# wbz451pe.net
KiCad netlist of a schematic drawn in EAGLE
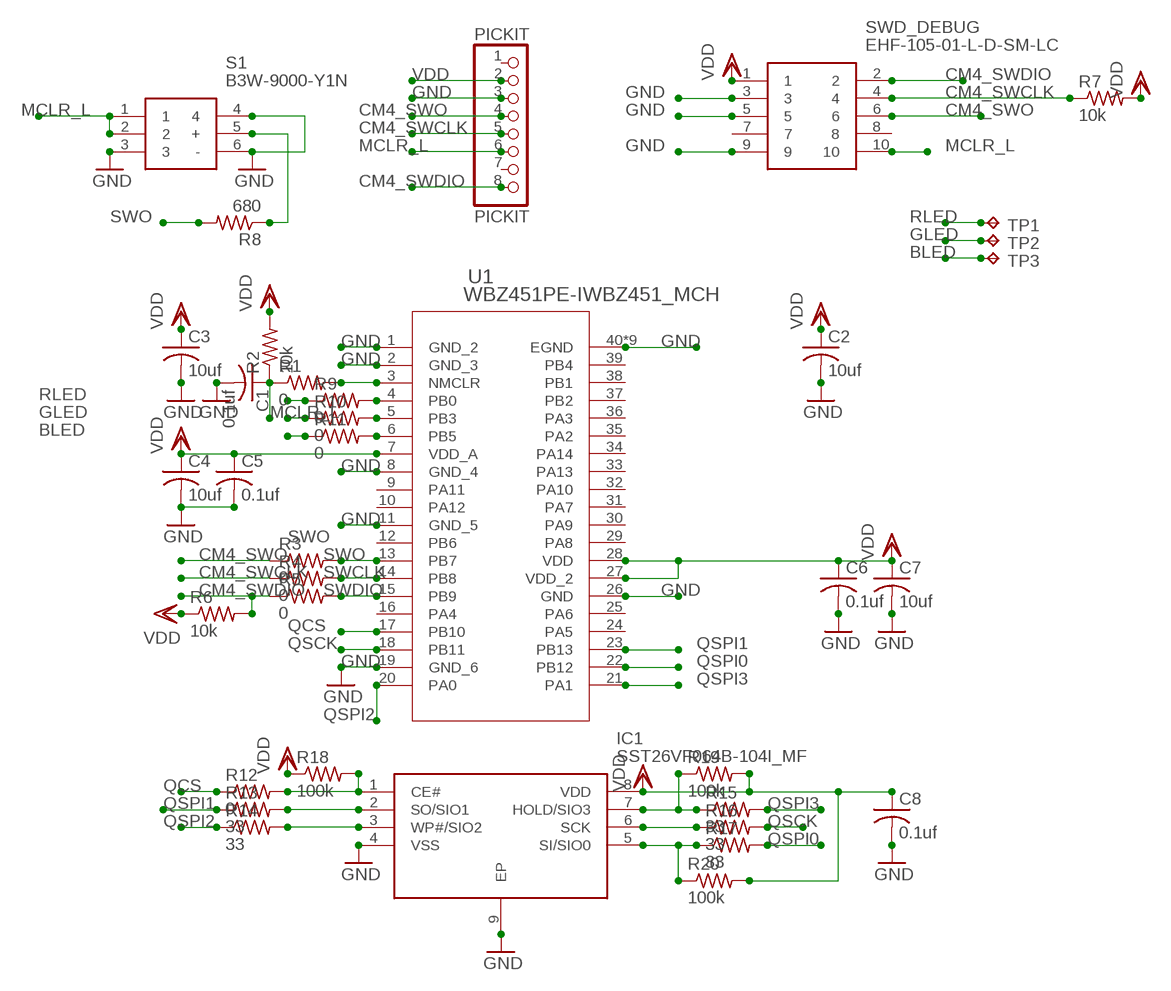
[diagram p0: schematic, sheet 1]

(export (version "E")
  (design (tool "Eeschema 10.0.6"))
  (components
    (comp (ref "C1")
      (value "0.1uf")
      (footprint "eagle-import:C0805")
      (libsource (lib "eagle-import") (part "C-USC0805"))
    )
    (comp (ref "C2")
      (value "10uf")
      (footprint "eagle-import:C0805")
      (libsource (lib "eagle-import") (part "C-USC0805"))
    )
    (comp (ref "C3")
      (value "10uf")
      (footprint "eagle-import:C0805")
      (libsource (lib "eagle-import") (part "C-USC0805"))
    )
    (comp (ref "C4")
      (value "10uf")
      (footprint "eagle-import:C0805")
      (libsource (lib "eagle-import") (part "C-USC0805"))
    )
    (comp (ref "C5")
      (value "0.1uf")
      (footprint "eagle-import:C0805")
      (libsource (lib "eagle-import") (part "C-USC0805"))
    )
    (comp (ref "C6")
      (value "0.1uf")
      (footprint "eagle-import:C0805")
      (libsource (lib "eagle-import") (part "C-USC0805"))
    )
    (comp (ref "C7")
      (value "10uf")
      (footprint "eagle-import:C0805")
      (libsource (lib "eagle-import") (part "C-USC0805"))
    )
    (comp (ref "C8")
      (value "0.1uf")
      (footprint "eagle-import:C0805")
      (libsource (lib "eagle-import") (part "C-USC0805"))
    )
    (comp (ref "IC1")
      (value "SST26VF064B-104I_MF")
      (footprint "eagle-import:SON127P600X500X80-9N")
      (fields
        (field (name "MANUFACTURER_PART_NUMBER") "SST26VF064B-104I/MF")
        (field (name "MOUSER_PART_NUMBER") "579-ST26VF064B104IMF")
      )
      (libsource (lib "eagle-import") (part "SST26VF064B-104I_MF"))
    )
    (comp (ref "PICKIT")
      (value "PICKIT")
      (footprint "eagle-import:1X08")
      (libsource (lib "eagle-import") (part "PINHD-1X8"))
    )
    (comp (ref "R1")
      (value "0")
      (footprint "eagle-import:M0805")
      (libsource (lib "eagle-import") (part "R-US_M0805"))
    )
    (comp (ref "R2")
      (value "10k")
      (footprint "eagle-import:M0805")
      (libsource (lib "eagle-import") (part "R-US_M0805"))
    )
    (comp (ref "R3")
      (value "0")
      (footprint "eagle-import:M0805")
      (libsource (lib "eagle-import") (part "R-US_M0805"))
    )
    (comp (ref "R4")
      (value "0")
      (footprint "eagle-import:M0805")
      (libsource (lib "eagle-import") (part "R-US_M0805"))
    )
    (comp (ref "R5")
      (value "0")
      (footprint "eagle-import:M0805")
      (libsource (lib "eagle-import") (part "R-US_M0805"))
    )
    (comp (ref "R6")
      (value "10k")
      (footprint "eagle-import:M0805")
      (libsource (lib "eagle-import") (part "R-US_M0805"))
    )
    (comp (ref "R7")
      (value "10k")
      (footprint "eagle-import:M0805")
      (libsource (lib "eagle-import") (part "R-US_M0805"))
    )
    (comp (ref "R8")
      (value "680")
      (footprint "eagle-import:M0805")
      (libsource (lib "eagle-import") (part "R-US_M0805"))
    )
    (comp (ref "R9")
      (value "0")
      (footprint "eagle-import:M0805")
      (libsource (lib "eagle-import") (part "R-US_M0805"))
    )
    (comp (ref "R10")
      (value "0")
      (footprint "eagle-import:M0805")
      (libsource (lib "eagle-import") (part "R-US_M0805"))
    )
    (comp (ref "R11")
      (value "0")
      (footprint "eagle-import:M0805")
      (libsource (lib "eagle-import") (part "R-US_M0805"))
    )
    (comp (ref "R12")
      (value "0")
      (footprint "eagle-import:R0603")
      (libsource (lib "eagle-import") (part "R-US_R0603"))
    )
    (comp (ref "R13")
      (value "33")
      (footprint "eagle-import:R0603")
      (libsource (lib "eagle-import") (part "R-US_R0603"))
    )
    (comp (ref "R14")
      (value "33")
      (footprint "eagle-import:R0603")
      (libsource (lib "eagle-import") (part "R-US_R0603"))
    )
    (comp (ref "R15")
      (value "33")
      (footprint "eagle-import:R0603")
      (libsource (lib "eagle-import") (part "R-US_R0603"))
    )
    (comp (ref "R16")
      (value "33")
      (footprint "eagle-import:R0603")
      (libsource (lib "eagle-import") (part "R-US_R0603"))
    )
    (comp (ref "R17")
      (value "33")
      (footprint "eagle-import:R0603")
      (libsource (lib "eagle-import") (part "R-US_R0603"))
    )
    (comp (ref "R18")
      (value "100k")
      (footprint "eagle-import:R0603")
      (libsource (lib "eagle-import") (part "R-US_R0603"))
    )
    (comp (ref "R19")
      (value "100k")
      (footprint "eagle-import:R0603")
      (libsource (lib "eagle-import") (part "R-US_R0603"))
    )
    (comp (ref "R20")
      (value "100k")
      (footprint "eagle-import:R0603")
      (libsource (lib "eagle-import") (part "R-US_R0603"))
    )
    (comp (ref "S1")
      (value "B3W-9000-Y1N")
      (footprint "eagle-import:B3W-9_1-LED")
      (fields
        (field (name "MOUSER_PART_NUMBER") "653-B3W-9000-Y1N")
        (field (name "RS_PART_NUMBER") "0492777P")
      )
      (libsource (lib "eagle-import") (part "B3W-9000-Y1N"))
    )
    (comp (ref "SWD_DEBUG")
      (value "EHF-105-01-L-D-SM-LC")
      (footprint "eagle-import:EHF-105-01-XX-D-SM-LC")
      (fields (field (name "MOUSER_PART_NUMBER") "200-EHF10501LDSMLC"))
      (libsource (lib "eagle-import") (part "EHF-105-01-L-D-SM-LC"))
    )
    (comp (ref "TP1")
      (value "TPPAD1-13")
      (footprint "eagle-import:P1-13")
      (libsource (lib "eagle-import") (part "TPPAD1-13"))
    )
    (comp (ref "TP2")
      (value "TPPAD1-13")
      (footprint "eagle-import:P1-13")
      (libsource (lib "eagle-import") (part "TPPAD1-13"))
    )
    (comp (ref "TP3")
      (value "TPPAD1-13")
      (footprint "eagle-import:P1-13")
      (libsource (lib "eagle-import") (part "TPPAD1-13"))
    )
    (comp (ref "U1")
      (value "WBZ451PE-IWBZ451_MCH")
      (footprint "eagle-import:WBZ451_MCH")
      (fields
        (field (name "MANUFACTURER_PART_NUMBER") "WBZ451PE-I")
        (field (name "COPYRIGHT") "Copyright (C) 2024 Ultra Librarian. All rights reserved.")
      )
      (libsource (lib "eagle-import") (part "WBZ451PE-IWBZ451_MCH"))
    )
  )
  (nets
    (net (code "1") (name "/BLED") (class "Default")
      (node (ref "R11") (pin "1") (pinfunction "1_1") (pintype "passive"))
      (node (ref "TP3") (pin "TP") (pinfunction "TP_TP") (pintype "input"))
    )
    (net (code "2") (name "/CM4_SWCLK") (class "Default")
      (node (ref "PICKIT") (pin "5") (pinfunction "5_5") (pintype "passive"))
      (node (ref "R4") (pin "1") (pinfunction "1_1") (pintype "passive"))
      (node (ref "R7") (pin "1") (pinfunction "1_1") (pintype "passive"))
      (node (ref "SWD_DEBUG") (pin "4") (pinfunction "4_4") (pintype "bidirectional"))
    )
    (net (code "3") (name "/CM4_SWDIO") (class "Default")
      (node (ref "PICKIT") (pin "8") (pinfunction "8_8") (pintype "passive"))
      (node (ref "R5") (pin "1") (pinfunction "1_1") (pintype "passive"))
      (node (ref "R6") (pin "2") (pinfunction "2_2") (pintype "passive"))
      (node (ref "SWD_DEBUG") (pin "2") (pinfunction "2_2") (pintype "bidirectional"))
    )
    (net (code "4") (name "/CM4_SWO") (class "Default")
      (node (ref "PICKIT") (pin "4") (pinfunction "4_4") (pintype "passive"))
      (node (ref "R3") (pin "1") (pinfunction "1_1") (pintype "passive"))
      (node (ref "SWD_DEBUG") (pin "6") (pinfunction "6_6") (pintype "bidirectional"))
    )
    (net (code "5") (name "/GLED") (class "Default")
      (node (ref "R10") (pin "1") (pinfunction "1_1") (pintype "passive"))
      (node (ref "TP2") (pin "TP") (pinfunction "TP_TP") (pintype "input"))
    )
    (net (code "6") (name "/MCLR_L") (class "Default")
      (node (ref "C1") (pin "1") (pinfunction "1_1") (pintype "passive"))
      (node (ref "PICKIT") (pin "6") (pinfunction "6_6") (pintype "passive"))
      (node (ref "R1") (pin "1") (pinfunction "1_1") (pintype "passive"))
      (node (ref "R2") (pin "1") (pinfunction "1_1") (pintype "passive"))
      (node (ref "S1") (pin "1") (pinfunction "1_1") (pintype "bidirectional"))
      (node (ref "S1") (pin "2") (pinfunction "2_2") (pintype "bidirectional"))
      (node (ref "SWD_DEBUG") (pin "10") (pinfunction "10_10") (pintype "bidirectional"))
    )
    (net (code "7") (name "/QCS") (class "Default")
      (node (ref "R12") (pin "1") (pinfunction "1_1") (pintype "passive"))
      (node (ref "U1") (pin "17") (pinfunction "PB10_17") (pintype "bidirectional"))
    )
    (net (code "8") (name "/QSCK") (class "Default")
      (node (ref "R16") (pin "2") (pinfunction "2_2") (pintype "passive"))
      (node (ref "U1") (pin "18") (pinfunction "PB11_18") (pintype "bidirectional"))
    )
    (net (code "9") (name "/QSPI0") (class "Default")
      (node (ref "R17") (pin "2") (pinfunction "2_2") (pintype "passive"))
      (node (ref "U1") (pin "22") (pinfunction "PB12_22") (pintype "bidirectional"))
    )
    (net (code "10") (name "/QSPI1") (class "Default")
      (node (ref "R13") (pin "1") (pinfunction "1_1") (pintype "passive"))
      (node (ref "U1") (pin "23") (pinfunction "PB13_23") (pintype "bidirectional"))
    )
    (net (code "11") (name "/QSPI2") (class "Default")
      (node (ref "R14") (pin "1") (pinfunction "1_1") (pintype "passive"))
      (node (ref "U1") (pin "20") (pinfunction "PA0_20") (pintype "bidirectional"))
    )
    (net (code "12") (name "/QSPI3") (class "Default")
      (node (ref "R15") (pin "2") (pinfunction "2_2") (pintype "passive"))
      (node (ref "U1") (pin "21") (pinfunction "PA1_21") (pintype "bidirectional"))
    )
    (net (code "13") (name "/RLED") (class "Default")
      (node (ref "R9") (pin "1") (pinfunction "1_1") (pintype "passive"))
      (node (ref "TP1") (pin "TP") (pinfunction "TP_TP") (pintype "input"))
    )
    (net (code "14") (name "/SWCLK") (class "Default")
      (node (ref "R4") (pin "2") (pinfunction "2_2") (pintype "passive"))
      (node (ref "U1") (pin "14") (pinfunction "PB8_14") (pintype "bidirectional"))
    )
    (net (code "15") (name "/SWDIO") (class "Default")
      (node (ref "R5") (pin "2") (pinfunction "2_2") (pintype "passive"))
      (node (ref "U1") (pin "15") (pinfunction "PB9_15") (pintype "bidirectional"))
    )
    (net (code "16") (name "/SWO") (class "Default")
      (node (ref "R3") (pin "2") (pinfunction "2_2") (pintype "passive"))
      (node (ref "R8") (pin "2") (pinfunction "2_2") (pintype "passive"))
      (node (ref "U1") (pin "13") (pinfunction "PB7_13") (pintype "bidirectional"))
    )
    (net (code "17") (name "GND") (class "Default")
      (node (ref "C1") (pin "2") (pinfunction "2_2") (pintype "passive"))
      (node (ref "C2") (pin "2") (pinfunction "2_2") (pintype "passive"))
      (node (ref "C3") (pin "2") (pinfunction "2_2") (pintype "passive"))
      (node (ref "C4") (pin "2") (pinfunction "2_2") (pintype "passive"))
      (node (ref "C5") (pin "2") (pinfunction "2_2") (pintype "passive"))
      (node (ref "C6") (pin "2") (pinfunction "2_2") (pintype "passive"))
      (node (ref "C7") (pin "2") (pinfunction "2_2") (pintype "passive"))
      (node (ref "C8") (pin "2") (pinfunction "2_2") (pintype "passive"))
      (node (ref "IC1") (pin "4") (pinfunction "VSS_4") (pintype "bidirectional"))
      (node (ref "IC1") (pin "9") (pinfunction "EP_9") (pintype "bidirectional"))
      (node (ref "PICKIT") (pin "3") (pinfunction "3_3") (pintype "passive"))
      (node (ref "S1") (pin "3") (pinfunction "3_3") (pintype "bidirectional"))
      (node (ref "S1") (pin "4") (pinfunction "4_4") (pintype "bidirectional"))
      (node (ref "S1") (pin "6") (pinfunction "-_6") (pintype "bidirectional"))
      (node (ref "SWD_DEBUG") (pin "3") (pinfunction "3_3") (pintype "bidirectional"))
      (node (ref "SWD_DEBUG") (pin "5") (pinfunction "5_5") (pintype "bidirectional"))
      (node (ref "SWD_DEBUG") (pin "9") (pinfunction "9_9") (pintype "bidirectional"))
      (node (ref "U1") (pin "1") (pinfunction "GND_2_1") (pintype "passive"))
      (node (ref "U1") (pin "11") (pinfunction "GND_5_11") (pintype "passive"))
      (node (ref "U1") (pin "19") (pinfunction "GND_6_19") (pintype "passive"))
      (node (ref "U1") (pin "2") (pinfunction "GND_3_2") (pintype "passive"))
      (node (ref "U1") (pin "26") (pinfunction "GND_26") (pintype "passive"))
      (node (ref "U1") (pin "40") (pinfunction "EGND_40") (pintype "passive"))
      (node (ref "U1") (pin "41") (pinfunction "EGND_41") (pintype "passive"))
      (node (ref "U1") (pin "42") (pinfunction "EGND_42") (pintype "passive"))
      (node (ref "U1") (pin "43") (pinfunction "EGND_43") (pintype "passive"))
      (node (ref "U1") (pin "44") (pinfunction "EGND_44") (pintype "passive"))
      (node (ref "U1") (pin "45") (pinfunction "EGND_45") (pintype "passive"))
      (node (ref "U1") (pin "46") (pinfunction "EGND_46") (pintype "passive"))
      (node (ref "U1") (pin "47") (pinfunction "EGND_47") (pintype "passive"))
      (node (ref "U1") (pin "48") (pinfunction "EGND_48") (pintype "passive"))
      (node (ref "U1") (pin "8") (pinfunction "GND_4_8") (pintype "passive"))
    )
    (net (code "18") (name "Net-(IC1-CE#)") (class "Default")
      (node (ref "IC1") (pin "1") (pinfunction "CE#_1") (pintype "bidirectional"))
      (node (ref "R12") (pin "2") (pinfunction "2_2") (pintype "passive"))
      (node (ref "R18") (pin "2") (pinfunction "2_2") (pintype "passive"))
    )
    (net (code "19") (name "Net-(IC1-HOLD{slash}SIO3)") (class "Default")
      (node (ref "IC1") (pin "7") (pinfunction "HOLD/SIO3_7") (pintype "bidirectional"))
      (node (ref "R15") (pin "1") (pinfunction "1_1") (pintype "passive"))
      (node (ref "R19") (pin "1") (pinfunction "1_1") (pintype "passive"))
    )
    (net (code "20") (name "Net-(IC1-SCK)") (class "Default")
      (node (ref "IC1") (pin "6") (pinfunction "SCK_6") (pintype "bidirectional"))
      (node (ref "R16") (pin "1") (pinfunction "1_1") (pintype "passive"))
    )
    (net (code "21") (name "Net-(IC1-SI{slash}SIO0)") (class "Default")
      (node (ref "IC1") (pin "5") (pinfunction "SI/SIO0_5") (pintype "bidirectional"))
      (node (ref "R17") (pin "1") (pinfunction "1_1") (pintype "passive"))
      (node (ref "R20") (pin "1") (pinfunction "1_1") (pintype "passive"))
    )
    (net (code "22") (name "Net-(IC1-SO{slash}SIO1)") (class "Default")
      (node (ref "IC1") (pin "2") (pinfunction "SO/SIO1_2") (pintype "bidirectional"))
      (node (ref "R13") (pin "2") (pinfunction "2_2") (pintype "passive"))
    )
    (net (code "23") (name "Net-(IC1-WP#{slash}SIO2)") (class "Default")
      (node (ref "IC1") (pin "3") (pinfunction "WP#/SIO2_3") (pintype "bidirectional"))
      (node (ref "R14") (pin "2") (pinfunction "2_2") (pintype "passive"))
    )
    (net (code "24") (name "Net-(S1-+)") (class "Default")
      (node (ref "R8") (pin "1") (pinfunction "1_1") (pintype "passive"))
      (node (ref "S1") (pin "5") (pinfunction "+_5") (pintype "bidirectional"))
    )
    (net (code "25") (name "Net-(U1-NMCLR)") (class "Default")
      (node (ref "R1") (pin "2") (pinfunction "2_2") (pintype "passive"))
      (node (ref "U1") (pin "3") (pinfunction "NMCLR_3") (pintype "input"))
    )
    (net (code "26") (name "Net-(U1-PB0)") (class "Default")
      (node (ref "R9") (pin "2") (pinfunction "2_2") (pintype "passive"))
      (node (ref "U1") (pin "4") (pinfunction "PB0_4") (pintype "bidirectional"))
    )
    (net (code "27") (name "Net-(U1-PB3)") (class "Default")
      (node (ref "R10") (pin "2") (pinfunction "2_2") (pintype "passive"))
      (node (ref "U1") (pin "5") (pinfunction "PB3_5") (pintype "bidirectional"))
    )
    (net (code "28") (name "Net-(U1-PB5)") (class "Default")
      (node (ref "R11") (pin "2") (pinfunction "2_2") (pintype "passive"))
      (node (ref "U1") (pin "6") (pinfunction "PB5_6") (pintype "bidirectional"))
    )
    (net (code "29") (name "VDD") (class "Default")
      (node (ref "C2") (pin "1") (pinfunction "1_1") (pintype "passive"))
      (node (ref "C3") (pin "1") (pinfunction "1_1") (pintype "passive"))
      (node (ref "C4") (pin "1") (pinfunction "1_1") (pintype "passive"))
      (node (ref "C5") (pin "1") (pinfunction "1_1") (pintype "passive"))
      (node (ref "C6") (pin "1") (pinfunction "1_1") (pintype "passive"))
      (node (ref "C7") (pin "1") (pinfunction "1_1") (pintype "passive"))
      (node (ref "C8") (pin "1") (pinfunction "1_1") (pintype "passive"))
      (node (ref "IC1") (pin "8") (pinfunction "VDD_8") (pintype "bidirectional"))
      (node (ref "PICKIT") (pin "2") (pinfunction "2_2") (pintype "passive"))
      (node (ref "R18") (pin "1") (pinfunction "1_1") (pintype "passive"))
      (node (ref "R19") (pin "2") (pinfunction "2_2") (pintype "passive"))
      (node (ref "R2") (pin "2") (pinfunction "2_2") (pintype "passive"))
      (node (ref "R20") (pin "2") (pinfunction "2_2") (pintype "passive"))
      (node (ref "R6") (pin "1") (pinfunction "1_1") (pintype "passive"))
      (node (ref "R7") (pin "2") (pinfunction "2_2") (pintype "passive"))
      (node (ref "SWD_DEBUG") (pin "1") (pinfunction "1_1") (pintype "bidirectional"))
      (node (ref "U1") (pin "27") (pinfunction "VDD_2_27") (pintype "power_in"))
      (node (ref "U1") (pin "28") (pinfunction "VDD_28") (pintype "power_in"))
      (node (ref "U1") (pin "7") (pinfunction "VDD_A_7") (pintype "power_in"))
    )
    (net (code "30") (name "unconnected-(PICKIT-Pad1)") (class "Default")
      (node (ref "PICKIT") (pin "1") (pinfunction "1_1") (pintype "passive"))
    )
    (net (code "31") (name "unconnected-(PICKIT-Pad7)") (class "Default")
      (node (ref "PICKIT") (pin "7") (pinfunction "7_7") (pintype "passive"))
    )
    (net (code "32") (name "unconnected-(SWD_DEBUG-Pad7)") (class "Default")
      (node (ref "SWD_DEBUG") (pin "7") (pinfunction "7_7") (pintype "bidirectional"))
    )
    (net (code "33") (name "unconnected-(SWD_DEBUG-Pad8)") (class "Default")
      (node (ref "SWD_DEBUG") (pin "8") (pinfunction "8_8") (pintype "bidirectional"))
    )
    (net (code "34") (name "unconnected-(U1-PA2-Pad35)") (class "Default")
      (node (ref "U1") (pin "35") (pinfunction "PA2_35") (pintype "bidirectional"))
    )
    (net (code "35") (name "unconnected-(U1-PA3-Pad36)") (class "Default")
      (node (ref "U1") (pin "36") (pinfunction "PA3_36") (pintype "bidirectional"))
    )
    (net (code "36") (name "unconnected-(U1-PA4-Pad16)") (class "Default")
      (node (ref "U1") (pin "16") (pinfunction "PA4_16") (pintype "bidirectional"))
    )
    (net (code "37") (name "unconnected-(U1-PA5-Pad24)") (class "Default")
      (node (ref "U1") (pin "24") (pinfunction "PA5_24") (pintype "bidirectional"))
    )
    (net (code "38") (name "unconnected-(U1-PA6-Pad25)") (class "Default")
      (node (ref "U1") (pin "25") (pinfunction "PA6_25") (pintype "bidirectional"))
    )
    (net (code "39") (name "unconnected-(U1-PA7-Pad31)") (class "Default")
      (node (ref "U1") (pin "31") (pinfunction "PA7_31") (pintype "bidirectional"))
    )
    (net (code "40") (name "unconnected-(U1-PA8-Pad29)") (class "Default")
      (node (ref "U1") (pin "29") (pinfunction "PA8_29") (pintype "bidirectional"))
    )
    (net (code "41") (name "unconnected-(U1-PA9-Pad30)") (class "Default")
      (node (ref "U1") (pin "30") (pinfunction "PA9_30") (pintype "bidirectional"))
    )
    (net (code "42") (name "unconnected-(U1-PA10-Pad32)") (class "Default")
      (node (ref "U1") (pin "32") (pinfunction "PA10_32") (pintype "bidirectional"))
    )
    (net (code "43") (name "unconnected-(U1-PA11-Pad9)") (class "Default")
      (node (ref "U1") (pin "9") (pinfunction "PA11_9") (pintype "bidirectional"))
    )
    (net (code "44") (name "unconnected-(U1-PA12-Pad10)") (class "Default")
      (node (ref "U1") (pin "10") (pinfunction "PA12_10") (pintype "bidirectional"))
    )
    (net (code "45") (name "unconnected-(U1-PA13-Pad33)") (class "Default")
      (node (ref "U1") (pin "33") (pinfunction "PA13_33") (pintype "bidirectional"))
    )
    (net (code "46") (name "unconnected-(U1-PA14-Pad34)") (class "Default")
      (node (ref "U1") (pin "34") (pinfunction "PA14_34") (pintype "bidirectional"))
    )
    (net (code "47") (name "unconnected-(U1-PB1-Pad38)") (class "Default")
      (node (ref "U1") (pin "38") (pinfunction "PB1_38") (pintype "bidirectional"))
    )
    (net (code "48") (name "unconnected-(U1-PB2-Pad37)") (class "Default")
      (node (ref "U1") (pin "37") (pinfunction "PB2_37") (pintype "bidirectional"))
    )
    (net (code "49") (name "unconnected-(U1-PB4-Pad39)") (class "Default")
      (node (ref "U1") (pin "39") (pinfunction "PB4_39") (pintype "bidirectional"))
    )
    (net (code "50") (name "unconnected-(U1-PB6-Pad12)") (class "Default")
      (node (ref "U1") (pin "12") (pinfunction "PB6_12") (pintype "bidirectional"))
    )
  )
)
